# KA2_6.net
KiCad netlist of a schematic drawn in Altium Designer
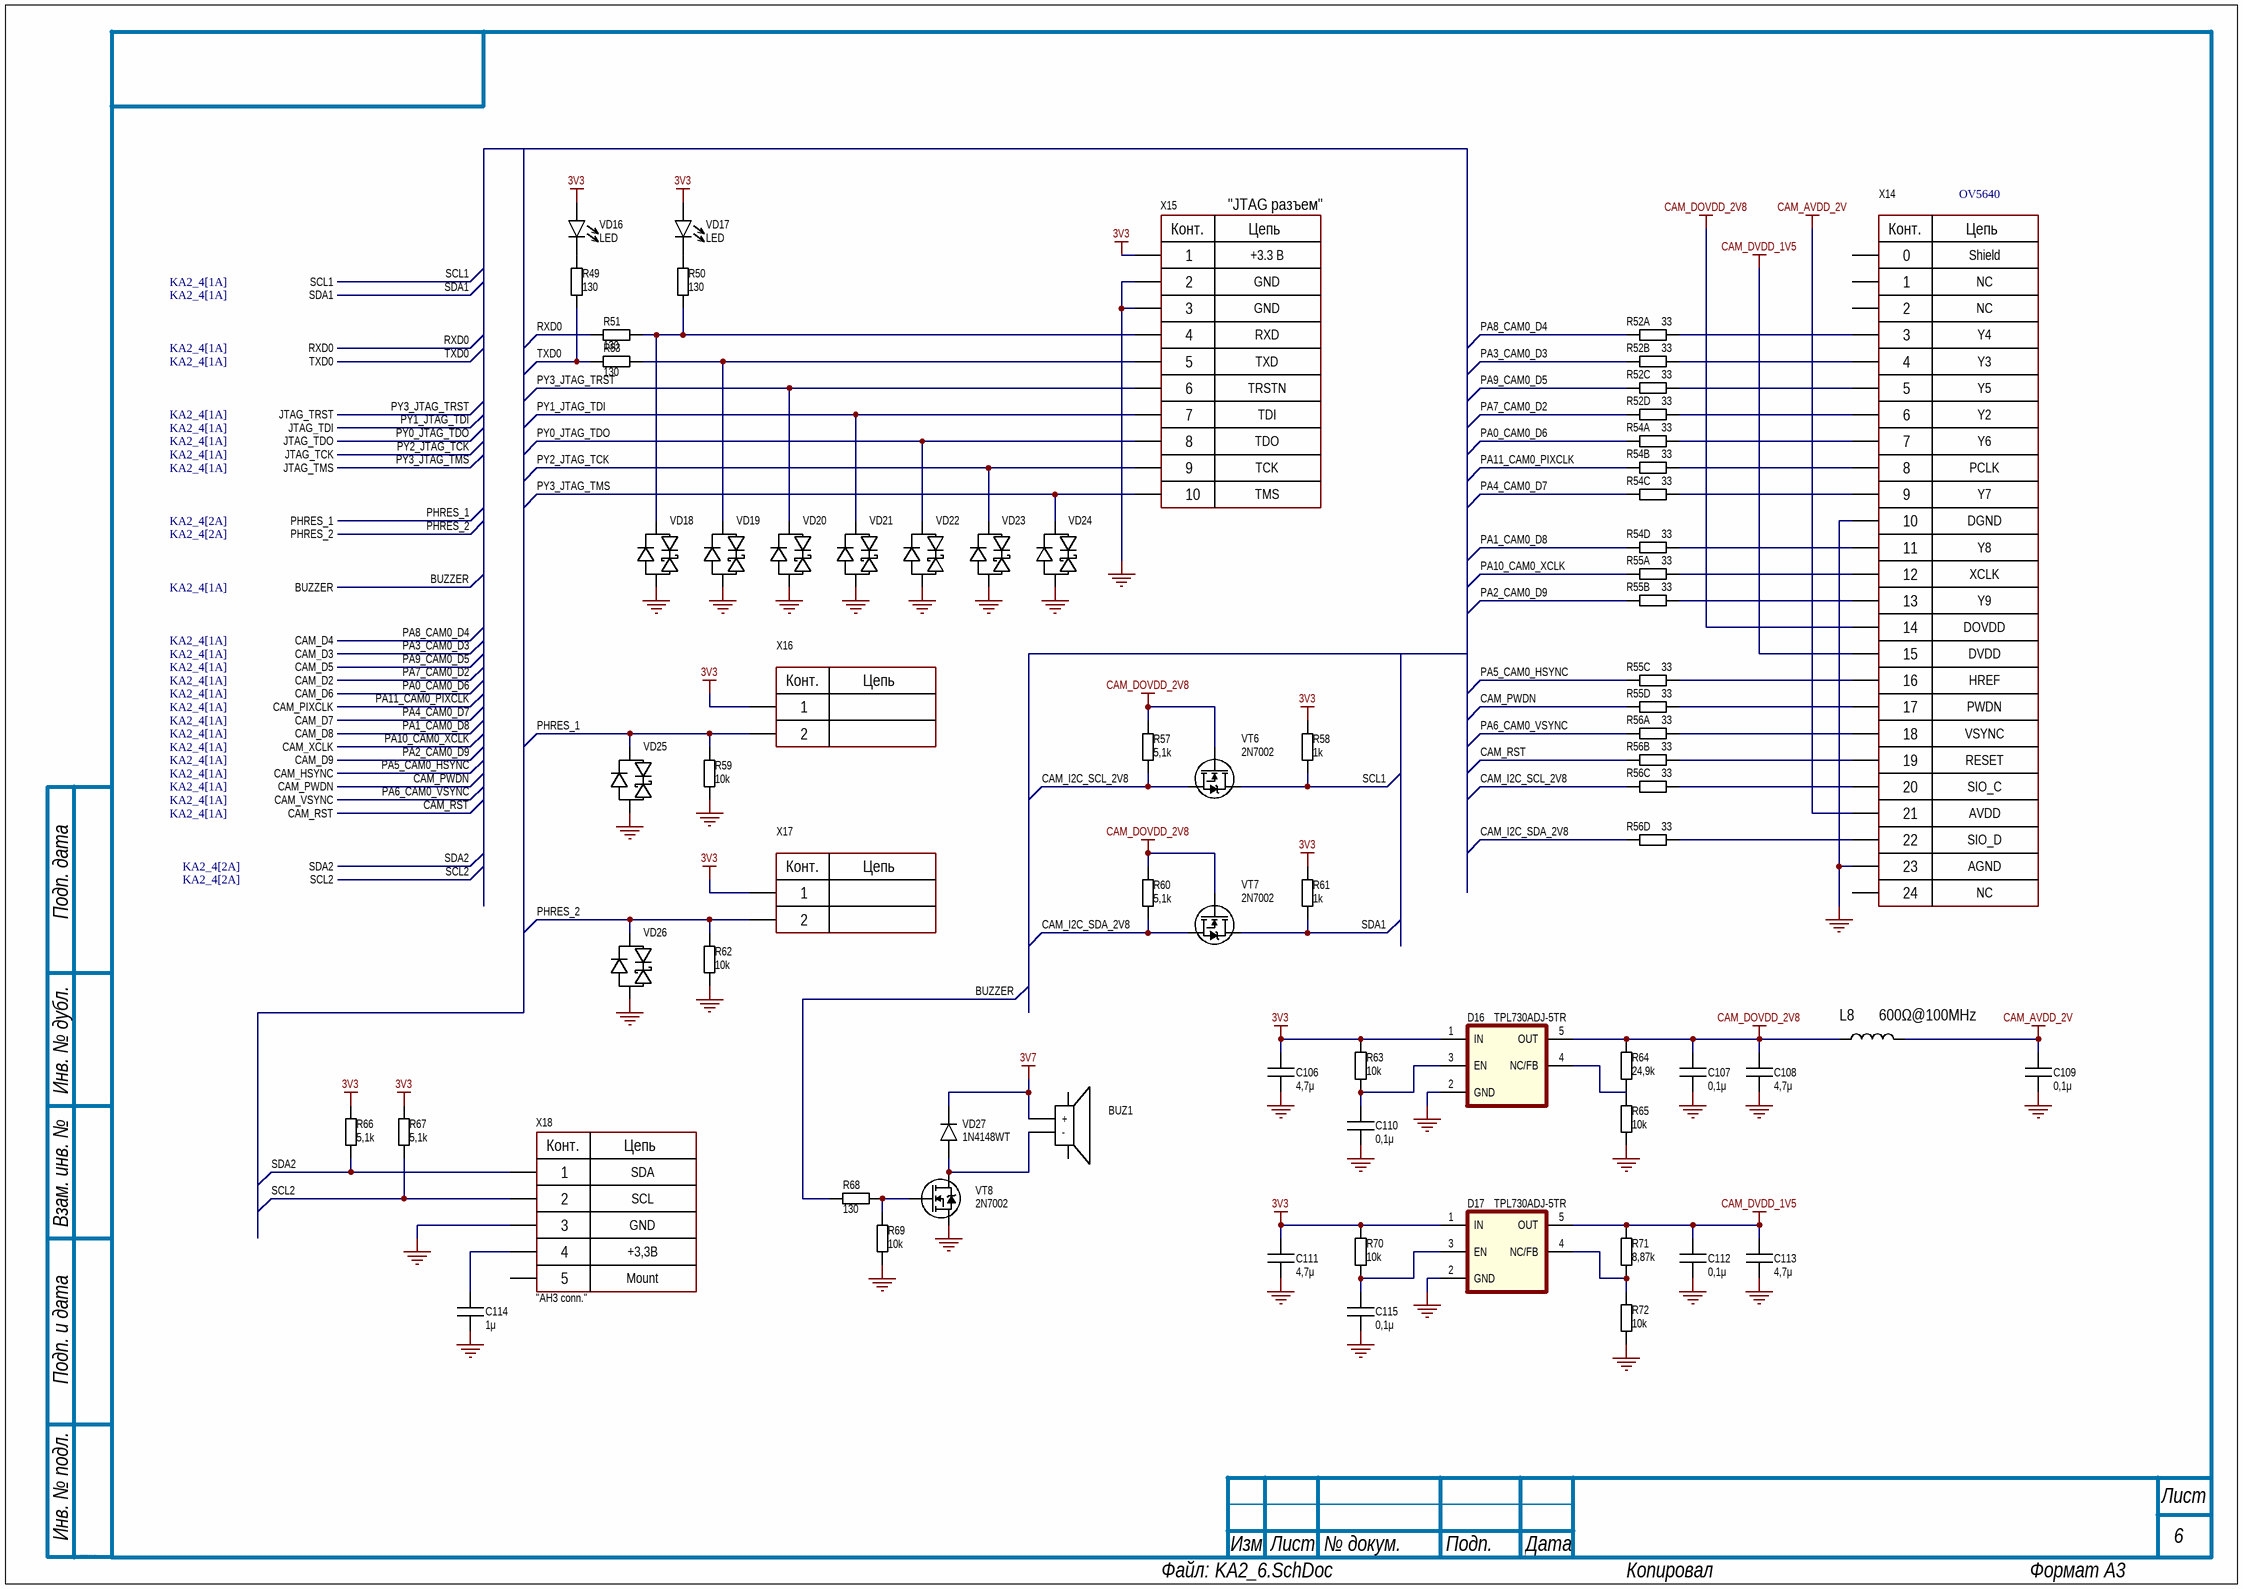
[diagram p0: KA2_6.SchDoc]

(export (version "E")
  (design (tool "Eeschema 10.0.6"))
  (components
    (comp (ref "BUZ1")
      (value "SMD7525-16Ohm")
      (footprint "BUZZER_SMD_7.5X7.5MM")
      (description "Буззер электромагнитный SMD, 7.5x7.5x2.5mm")
      (fields (field (name "MANUFACTURER") "XHXDZ") (field (name "MFR.PART") "SMD7525-16Ω"))
      (libsource (lib "Barsotion") (part "SMD7525-16Ohm"))
    )
    (comp (ref "C106")
      (value "4,7μ")
      (footprint "Capacitor_0402")
      (fields
        (field (name "VALUEMANUFACTURERPARTNUMBER") "Ceramic capacitor, 4,7μ, X7R, ±10%, 16V, 0402")
        (field (name "TOLERANCE") "±10%")
        (field (name "VOLTAGE") "16V")
      )
      (libsource (lib "Barsotion") (part "Ceramic_0402"))
    )
    (comp (ref "C107")
      (value "0,1μ")
      (footprint "Capacitor_0402")
      (fields
        (field (name "VALUEMANUFACTURERPARTNUMBER") "Ceramic capacitor, 0,1μ, X7R, ±10%, 16V, 0402")
        (field (name "TOLERANCE") "±10%")
        (field (name "VOLTAGE") "16V")
      )
      (libsource (lib "Barsotion") (part "Ceramic_0402"))
    )
    (comp (ref "C108")
      (value "4,7μ")
      (footprint "Capacitor_0402")
      (fields
        (field (name "VALUEMANUFACTURERPARTNUMBER") "Ceramic capacitor, 4,7μ, X7R, ±10%, 16V, 0402")
        (field (name "TOLERANCE") "±10%")
        (field (name "VOLTAGE") "16V")
      )
      (libsource (lib "Barsotion") (part "Ceramic_0402"))
    )
    (comp (ref "C109")
      (value "0,1μ")
      (footprint "Capacitor_0402")
      (fields
        (field (name "VALUEMANUFACTURERPARTNUMBER") "Ceramic capacitor, 0,1μ, X7R, ±10%, 16V, 0402")
        (field (name "TOLERANCE") "±10%")
        (field (name "VOLTAGE") "16V")
      )
      (libsource (lib "Barsotion") (part "Ceramic_0402"))
    )
    (comp (ref "C110")
      (value "0,1μ")
      (footprint "Capacitor_0402")
      (fields
        (field (name "VALUEMANUFACTURERPARTNUMBER") "Ceramic capacitor, 0,1μ, X7R, ±10%, 16V, 0402")
        (field (name "TOLERANCE") "±10%")
        (field (name "VOLTAGE") "16V")
      )
      (libsource (lib "Barsotion") (part "Ceramic_0402"))
    )
    (comp (ref "C111")
      (value "4,7μ")
      (footprint "Capacitor_0402")
      (fields
        (field (name "VALUEMANUFACTURERPARTNUMBER") "Ceramic capacitor, 4,7μ, X7R, ±10%, 16V, 0402")
        (field (name "TOLERANCE") "±10%")
        (field (name "VOLTAGE") "16V")
      )
      (libsource (lib "Barsotion") (part "Ceramic_0402"))
    )
    (comp (ref "C112")
      (value "0,1μ")
      (footprint "Capacitor_0402")
      (fields
        (field (name "VALUEMANUFACTURERPARTNUMBER") "Ceramic capacitor, 0,1μ, X7R, ±10%, 16V, 0402")
        (field (name "TOLERANCE") "±10%")
        (field (name "VOLTAGE") "16V")
      )
      (libsource (lib "Barsotion") (part "Ceramic_0402"))
    )
    (comp (ref "C113")
      (value "4,7μ")
      (footprint "Capacitor_0402")
      (fields
        (field (name "VALUEMANUFACTURERPARTNUMBER") "Ceramic capacitor, 4,7μ, X7R, ±10%, 16V, 0402")
        (field (name "TOLERANCE") "±10%")
        (field (name "VOLTAGE") "16V")
      )
      (libsource (lib "Barsotion") (part "Ceramic_0402"))
    )
    (comp (ref "C114")
      (value "1μ")
      (footprint "Capacitor_0402")
      (fields
        (field (name "VALUEMANUFACTURERPARTNUMBER") "Ceramic capacitor, 1μ, X7R, ±10%, 16V, 0402")
        (field (name "TOLERANCE") "±10%")
        (field (name "VOLTAGE") "16V")
      )
      (libsource (lib "Barsotion") (part "Ceramic_0402"))
    )
    (comp (ref "C115")
      (value "0,1μ")
      (footprint "Capacitor_0402")
      (fields
        (field (name "VALUEMANUFACTURERPARTNUMBER") "Ceramic capacitor, 0,1μ, X7R, ±10%, 16V, 0402")
        (field (name "TOLERANCE") "±10%")
        (field (name "VOLTAGE") "16V")
      )
      (libsource (lib "Barsotion") (part "Ceramic_0402"))
    )
    (comp (ref "D16")
      (value "TPL730ADJ-5TR")
      (footprint "SOT-23-5")
      (description "Микросхема драйвера импульсного понижающего преобразователя")
      (fields (field (name "MANUFACTURER") "3PEAK") (field (name "Comment") "TPL730ADJ-5TL"))
      (libsource (lib "Barsotion") (part "TPL730ADJ-5TL"))
    )
    (comp (ref "D17")
      (value "TPL730ADJ-5TR")
      (footprint "SOT-23-5")
      (description "Микросхема драйвера импульсного понижающего преобразователя")
      (fields (field (name "MANUFACTURER") "3PEAK") (field (name "Comment") "TPL730ADJ-5TL"))
      (libsource (lib "Barsotion") (part "TPL730ADJ-5TL"))
    )
    (comp (ref "L8")
      (value "600Ω@100MHz")
      (footprint "IND: 0603")
      (fields
        (field (name "TOLERANCE") "±10%")
        (field (name "VALUEMANUFACTURERPARTNUMBER") "Inductor, 600Ω@100MHz, ±10%, 0603")
      )
      (libsource (lib "Barsotion") (part "Inductor_0603"))
    )
    (comp (ref "R49")
      (value "130")
      (footprint "RES: 0402")
      (fields
        (field (name "VALUEMANUFACTURERPARTNUMBER") "Resistor, 130, ±1%, 0402")
        (field (name "TOLERANCE") "±1%")
      )
      (libsource (lib "Barsotion") (part "Resistor_0402"))
    )
    (comp (ref "R50")
      (value "130")
      (footprint "RES: 0402")
      (fields
        (field (name "VALUEMANUFACTURERPARTNUMBER") "Resistor, 130, ±1%, 0402")
        (field (name "TOLERANCE") "±1%")
      )
      (libsource (lib "Barsotion") (part "Resistor_0402"))
    )
    (comp (ref "R51")
      (value "130")
      (footprint "RES: 0402")
      (fields
        (field (name "VALUEMANUFACTURERPARTNUMBER") "Resistor, 130, ±1%, 0402")
        (field (name "TOLERANCE") "±1%")
      )
      (libsource (lib "") (part "Resistor_0402_1"))
    )
    (comp (ref "R52")
      (value "33")
      (footprint "Resistor:RES: Array 4x0402")
      (fields
        (field (name "VALUEMANUFACTURERPARTNUMBER") "Resistor array (4), 33, ±1%, 0402")
        (field (name "TOLERANCE") "±1%")
      )
      (libsource (lib "Barsotion") (part "ResistorArray_0402_4"))
    )
    (comp (ref "R53")
      (value "130")
      (footprint "RES: 0402")
      (fields
        (field (name "VALUEMANUFACTURERPARTNUMBER") "Resistor, 130, ±1%, 0402")
        (field (name "TOLERANCE") "±1%")
      )
      (libsource (lib "") (part "Resistor_0402_1"))
    )
    (comp (ref "R54")
      (value "33")
      (footprint "Resistor:RES: Array 4x0402")
      (fields
        (field (name "VALUEMANUFACTURERPARTNUMBER") "Resistor array (4), 33, ±1%, 0402")
        (field (name "TOLERANCE") "±1%")
      )
      (libsource (lib "Barsotion") (part "ResistorArray_0402_4"))
    )
    (comp (ref "R55")
      (value "33")
      (footprint "Resistor:RES: Array 4x0402")
      (fields
        (field (name "VALUEMANUFACTURERPARTNUMBER") "Resistor array (4), 33, ±1%, 0402")
        (field (name "TOLERANCE") "±1%")
      )
      (libsource (lib "Barsotion") (part "ResistorArray_0402_4"))
    )
    (comp (ref "R56")
      (value "33")
      (footprint "Resistor:RES: Array 4x0402")
      (fields
        (field (name "VALUEMANUFACTURERPARTNUMBER") "Resistor array (4), 33, ±1%, 0402")
        (field (name "TOLERANCE") "±1%")
      )
      (libsource (lib "Barsotion") (part "ResistorArray_0402_4"))
    )
    (comp (ref "R57")
      (value "5,1k")
      (footprint "RES: 0402")
      (fields
        (field (name "VALUEMANUFACTURERPARTNUMBER") "Resistor, 5,1k, ±1%, 0402")
        (field (name "TOLERANCE") "±1%")
      )
      (libsource (lib "Barsotion") (part "Resistor_0402"))
    )
    (comp (ref "R58")
      (value "1k")
      (footprint "RES: 0402")
      (fields
        (field (name "VALUEMANUFACTURERPARTNUMBER") "Resistor, 1k, ±1%, 0402")
        (field (name "TOLERANCE") "±1%")
      )
      (libsource (lib "Barsotion") (part "Resistor_0402"))
    )
    (comp (ref "R59")
      (value "10k")
      (footprint "RES: 0402")
      (fields
        (field (name "VALUEMANUFACTURERPARTNUMBER") "Resistor, 10k, ±1%, 0402")
        (field (name "TOLERANCE") "±1%")
      )
      (libsource (lib "Barsotion") (part "Resistor_0402"))
    )
    (comp (ref "R60")
      (value "5,1k")
      (footprint "RES: 0402")
      (fields
        (field (name "VALUEMANUFACTURERPARTNUMBER") "Resistor, 5,1k, ±1%, 0402")
        (field (name "TOLERANCE") "±1%")
      )
      (libsource (lib "Barsotion") (part "Resistor_0402"))
    )
    (comp (ref "R61")
      (value "1k")
      (footprint "RES: 0402")
      (fields
        (field (name "VALUEMANUFACTURERPARTNUMBER") "Resistor, 1k, ±1%, 0402")
        (field (name "TOLERANCE") "±1%")
      )
      (libsource (lib "Barsotion") (part "Resistor_0402"))
    )
    (comp (ref "R62")
      (value "10k")
      (footprint "RES: 0402")
      (fields
        (field (name "VALUEMANUFACTURERPARTNUMBER") "Resistor, 10k, ±1%, 0402")
        (field (name "TOLERANCE") "±1%")
      )
      (libsource (lib "Barsotion") (part "Resistor_0402"))
    )
    (comp (ref "R63")
      (value "10k")
      (footprint "RES: 0402")
      (fields
        (field (name "VALUEMANUFACTURERPARTNUMBER") "Resistor, 10k, ±1%, 0402")
        (field (name "TOLERANCE") "±1%")
      )
      (libsource (lib "Barsotion") (part "Resistor_0402"))
    )
    (comp (ref "R64")
      (value "24,9k")
      (footprint "RES: 0402")
      (fields
        (field (name "VALUEMANUFACTURERPARTNUMBER") "Resistor, 24,9k, ±1%, 0402")
        (field (name "TOLERANCE") "±1%")
      )
      (libsource (lib "Barsotion") (part "Resistor_0402"))
    )
    (comp (ref "R65")
      (value "10k")
      (footprint "RES: 0402")
      (fields
        (field (name "VALUEMANUFACTURERPARTNUMBER") "Resistor, 10k, ±1%, 0402")
        (field (name "TOLERANCE") "±1%")
      )
      (libsource (lib "Barsotion") (part "Resistor_0402"))
    )
    (comp (ref "R66")
      (value "5,1k")
      (footprint "RES: 0402")
      (fields
        (field (name "VALUEMANUFACTURERPARTNUMBER") "Resistor, 5,1k, ±1%, 0402")
        (field (name "TOLERANCE") "±1%")
      )
      (libsource (lib "Barsotion") (part "Resistor_0402"))
    )
    (comp (ref "R67")
      (value "5,1k")
      (footprint "RES: 0402")
      (fields
        (field (name "VALUEMANUFACTURERPARTNUMBER") "Resistor, 5,1k, ±1%, 0402")
        (field (name "TOLERANCE") "±1%")
      )
      (libsource (lib "Barsotion") (part "Resistor_0402"))
    )
    (comp (ref "R68")
      (value "130")
      (footprint "RES: 0402")
      (fields
        (field (name "VALUEMANUFACTURERPARTNUMBER") "Resistor, 130, ±1%, 0402")
        (field (name "TOLERANCE") "±1%")
      )
      (libsource (lib "") (part "Resistor_0402_1"))
    )
    (comp (ref "R69")
      (value "10k")
      (footprint "RES: 0402")
      (fields
        (field (name "VALUEMANUFACTURERPARTNUMBER") "Resistor, 10k, ±1%, 0402")
        (field (name "TOLERANCE") "±1%")
      )
      (libsource (lib "Barsotion") (part "Resistor_0402"))
    )
    (comp (ref "R70")
      (value "10k")
      (footprint "RES: 0402")
      (fields
        (field (name "VALUEMANUFACTURERPARTNUMBER") "Resistor, 10k, ±1%, 0402")
        (field (name "TOLERANCE") "±1%")
      )
      (libsource (lib "Barsotion") (part "Resistor_0402"))
    )
    (comp (ref "R71")
      (value "8,87k")
      (footprint "RES: 0402")
      (fields
        (field (name "VALUEMANUFACTURERPARTNUMBER") "Resistor, 8,87k, ±1%, 0402")
        (field (name "TOLERANCE") "±1%")
      )
      (libsource (lib "Barsotion") (part "Resistor_0402"))
    )
    (comp (ref "R72")
      (value "10k")
      (footprint "RES: 0402")
      (fields
        (field (name "VALUEMANUFACTURERPARTNUMBER") "Resistor, 10k, ±1%, 0402")
        (field (name "TOLERANCE") "±1%")
      )
      (libsource (lib "Barsotion") (part "Resistor_0402"))
    )
    (comp (ref "VD16")
      (value "LED")
      (footprint "LED: 0603Y")
      (description "Светодиод ледяной синий, 0603")
      (fields (field (name "MFR.PART") "A-SP192GB1D-A02-4T") (field (name "MANUFACTURER") "Amicc"))
      (libsource (lib "Barsotion") (part "LED_0603_IB"))
    )
    (comp (ref "VD17")
      (value "LED")
      (footprint "LED: 0603Y")
      (description "Светодиод изумрудно-зеленый, 0603")
      (fields (field (name "MFR.PART") "XL-1608UGC-04") (field (name "MANUFACTURER") "XINGLIGHT"))
      (libsource (lib "Barsotion") (part "LED_0603_EG"))
    )
    (comp (ref "VD18")
      (value "D1213A-01T")
      (footprint "SOD-523")
      (fields (field (name "MANUFACTURER") "Diodes") (field (name "MFR.PART") "D1213A-01T-7"))
      (libsource (lib "Barsotion") (part "D1213A-01T"))
    )
    (comp (ref "VD19")
      (value "D1213A-01T")
      (footprint "SOD-523")
      (fields (field (name "MANUFACTURER") "Diodes") (field (name "MFR.PART") "D1213A-01T-7"))
      (libsource (lib "Barsotion") (part "D1213A-01T"))
    )
    (comp (ref "VD20")
      (value "D1213A-01T")
      (footprint "SOD-523")
      (fields (field (name "MANUFACTURER") "Diodes") (field (name "MFR.PART") "D1213A-01T-7"))
      (libsource (lib "Barsotion") (part "D1213A-01T"))
    )
    (comp (ref "VD21")
      (value "D1213A-01T")
      (footprint "SOD-523")
      (fields (field (name "MANUFACTURER") "Diodes") (field (name "MFR.PART") "D1213A-01T-7"))
      (libsource (lib "Barsotion") (part "D1213A-01T"))
    )
    (comp (ref "VD22")
      (value "D1213A-01T")
      (footprint "SOD-523")
      (fields (field (name "MANUFACTURER") "Diodes") (field (name "MFR.PART") "D1213A-01T-7"))
      (libsource (lib "Barsotion") (part "D1213A-01T"))
    )
    (comp (ref "VD23")
      (value "D1213A-01T")
      (footprint "SOD-523")
      (fields (field (name "MANUFACTURER") "Diodes") (field (name "MFR.PART") "D1213A-01T-7"))
      (libsource (lib "Barsotion") (part "D1213A-01T"))
    )
    (comp (ref "VD24")
      (value "D1213A-01T")
      (footprint "SOD-523")
      (fields (field (name "MANUFACTURER") "Diodes") (field (name "MFR.PART") "D1213A-01T-7"))
      (libsource (lib "Barsotion") (part "D1213A-01T"))
    )
    (comp (ref "VD25")
      (value "D1213A-01T")
      (footprint "SOD-523")
      (fields (field (name "MANUFACTURER") "Diodes") (field (name "MFR.PART") "D1213A-01T-7"))
      (libsource (lib "Barsotion") (part "D1213A-01T"))
    )
    (comp (ref "VD26")
      (value "D1213A-01T")
      (footprint "SOD-523")
      (fields (field (name "MANUFACTURER") "Diodes") (field (name "MFR.PART") "D1213A-01T-7"))
      (libsource (lib "Barsotion") (part "D1213A-01T"))
    )
    (comp (ref "VD27")
      (value "1N4148WT")
      (footprint "SOD-523")
      (description "Диод кремниевый 100В 300мА, SOD-123")
      (fields
        (field (name "MANUFACTURER") "JSMSEMI")
        (field (name "Comment") "Diode Independent 75V 150mA Surface Mount SOD-523")
      )
      (libsource (lib "Barsotion") (part "1N4148WT"))
    )
    (comp (ref "VT6")
      (value "2N7002")
      (footprint "SOT-23")
      (description "Транзистор N-канальный, 60В 115мА 200мВт, SOT-23")
      (fields (field (name "MFR.PART") "2N7002K-7") (field (name "MANUFACTURER") "Diodes"))
      (libsource (lib "Barsotion") (part "2N7002"))
    )
    (comp (ref "VT7")
      (value "2N7002")
      (footprint "SOT-23")
      (description "Транзистор N-канальный, 60В 115мА 200мВт, SOT-23")
      (fields (field (name "MFR.PART") "2N7002K-7") (field (name "MANUFACTURER") "Diodes"))
      (libsource (lib "Barsotion") (part "2N7002"))
    )
    (comp (ref "VT8")
      (value "2N7002")
      (footprint "SOT-23")
      (description "Транзистор N-канальный, 60В 115мА 200мВт, SOT-23")
      (fields (field (name "MFR.PART") "2N7002K-7") (field (name "MANUFACTURER") "Diodes"))
      (libsource (lib "Barsotion") (part "2N7002"))
    )
    (comp (ref "X14")
      (value "OV5640")
      (footprint "OV5640_CONNECTOR")
      (fields
        (field (name "MANUFACTURER") "kinghelm")
        (field (name "MFR.PART") "KH-FG0.5-H2.0-24PIN")
        (field (name "Comment") "Connector_OV5640")
      )
      (libsource (lib "Barsotion") (part "Connector_OV5640"))
    )
    (comp (ref "X15")
      (value "~")
      (footprint "CONN_5x10_1.27мм_NO_SOLDERING")
      (description "Edge-board JTAG connector including TRST")
      (fields
        (field (name "MANUFACTURER") "JST")
        (field (name "VALUEMANUFACTURERPARTNUMBER") "Connector, 2pin, 2.5 mm, 250V, 3A")
        (field (name "COMMENTTEXT") "\"JTAG разъем\"")
      )
      (libsource (lib "Barsotion") (part "Connector_JTAG_10"))
    )
    (comp (ref "X16")
      (value "Connector_JST_XH_B2B-XH-A_1x02_2.50mm")
      (footprint "CONN_JST_XH_B2B-XH-A_1x02_P2.50mm")
      (description "2-pin through-hole connector")
      (libsource (lib "Barsotion") (part "Connector_JST_XH_B2B-XH-A_1x02_2.50mm"))
    )
    (comp (ref "X17")
      (value "Connector_JST_XH_B2B-XH-A_1x02_2.50mm")
      (footprint "CONN_JST_XH_B2B-XH-A_1x02_P2.50mm")
      (description "2-pin through-hole connector")
      (libsource (lib "Barsotion") (part "Connector_JST_XH_B2B-XH-A_1x02_2.50mm"))
    )
    (comp (ref "X18")
      (value "\"AH3 conn.\"")
      (footprint "CONN_JST_GH_SM04B")
      (description "Connector Header 4 position 1.25mm Pitch")
      (fields
        (field (name "MANUFACTURER") "CJT(Changjiang Connectors)")
        (field (name "MFR.PART") "A1257WR-S-4P")
      )
      (libsource (lib "Barsotion") (part "Connector_AH3"))
    )
  )
  (nets
    (net (code "1") (name "/BUZZER") (class "Default")
      (node (ref "R68") (pin "2") (pinfunction "2_2") (pintype "passive"))
    )
    (net (code "2") (name "/CAM_I2C_SCL_2V8") (class "Default")
      (node (ref "R56") (pin "3") (pinfunction "3_3") (pintype "passive"))
      (node (ref "R57") (pin "1") (pinfunction "1_1") (pintype "passive"))
      (node (ref "VT6") (pin "2") (pinfunction "S_2") (pintype "passive"))
    )
    (net (code "3") (name "/CAM_I2C_SDA_2V8") (class "Default")
      (node (ref "R56") (pin "4") (pinfunction "4_4") (pintype "passive"))
      (node (ref "R60") (pin "1") (pinfunction "1_1") (pintype "passive"))
      (node (ref "VT7") (pin "2") (pinfunction "S_2") (pintype "passive"))
    )
    (net (code "4") (name "/CAM_PWDN") (class "Default")
      (node (ref "R55") (pin "4") (pinfunction "4_4") (pintype "passive"))
    )
    (net (code "5") (name "/CAM_RST") (class "Default")
      (node (ref "R56") (pin "2") (pinfunction "2_2") (pintype "passive"))
    )
    (net (code "6") (name "/PA0_CAM0_D6") (class "Default")
      (node (ref "R54") (pin "1") (pinfunction "1_1") (pintype "passive"))
    )
    (net (code "7") (name "/PA1_CAM0_D8") (class "Default")
      (node (ref "R54") (pin "4") (pinfunction "4_4") (pintype "passive"))
    )
    (net (code "8") (name "/PA2_CAM0_D9") (class "Default")
      (node (ref "R55") (pin "2") (pinfunction "2_2") (pintype "passive"))
    )
    (net (code "9") (name "/PA3_CAM0_D3") (class "Default")
      (node (ref "R52") (pin "2") (pinfunction "2_2") (pintype "passive"))
    )
    (net (code "10") (name "/PA4_CAM0_D7") (class "Default")
      (node (ref "R54") (pin "3") (pinfunction "3_3") (pintype "passive"))
    )
    (net (code "11") (name "/PA5_CAM0_HSYNC") (class "Default")
      (node (ref "R55") (pin "3") (pinfunction "3_3") (pintype "passive"))
    )
    (net (code "12") (name "/PA6_CAM0_VSYNC") (class "Default")
      (node (ref "R56") (pin "1") (pinfunction "1_1") (pintype "passive"))
    )
    (net (code "13") (name "/PA7_CAM0_D2") (class "Default")
      (node (ref "R52") (pin "4") (pinfunction "4_4") (pintype "passive"))
    )
    (net (code "14") (name "/PA8_CAM0_D4") (class "Default")
      (node (ref "R52") (pin "1") (pinfunction "1_1") (pintype "passive"))
    )
    (net (code "15") (name "/PA9_CAM0_D5") (class "Default")
      (node (ref "R52") (pin "3") (pinfunction "3_3") (pintype "passive"))
    )
    (net (code "16") (name "/PA10_CAM0_XCLK") (class "Default")
      (node (ref "R55") (pin "1") (pinfunction "1_1") (pintype "passive"))
    )
    (net (code "17") (name "/PA11_CAM0_PIXCLK") (class "Default")
      (node (ref "R54") (pin "2") (pinfunction "2_2") (pintype "passive"))
    )
    (net (code "18") (name "/PHRES_1") (class "Default")
      (node (ref "R59") (pin "2") (pinfunction "2_2") (pintype "passive"))
      (node (ref "VD25") (pin "K") (pinfunction "K_K") (pintype "passive"))
      (node (ref "X16") (pin "2") (pinfunction "2_2") (pintype "passive"))
    )
    (net (code "19") (name "/PHRES_2") (class "Default")
      (node (ref "R62") (pin "2") (pinfunction "2_2") (pintype "passive"))
      (node (ref "VD26") (pin "K") (pinfunction "K_K") (pintype "passive"))
      (node (ref "X17") (pin "2") (pinfunction "2_2") (pintype "passive"))
    )
    (net (code "20") (name "/PY0_JTAG_TDO") (class "Default")
      (node (ref "VD22") (pin "K") (pinfunction "K_K") (pintype "passive"))
      (node (ref "X15") (pin "8") (pinfunction "8_8") (pintype "passive"))
    )
    (net (code "21") (name "/PY1_JTAG_TDI") (class "Default")
      (node (ref "VD21") (pin "K") (pinfunction "K_K") (pintype "passive"))
      (node (ref "X15") (pin "7") (pinfunction "7_7") (pintype "passive"))
    )
    (net (code "22") (name "/PY2_JTAG_TCK") (class "Default")
      (node (ref "VD23") (pin "K") (pinfunction "K_K") (pintype "passive"))
      (node (ref "X15") (pin "9") (pinfunction "9_9") (pintype "passive"))
    )
    (net (code "23") (name "/PY3_JTAG_TMS") (class "Default")
      (node (ref "VD24") (pin "K") (pinfunction "K_K") (pintype "passive"))
      (node (ref "X15") (pin "10") (pinfunction "10_10") (pintype "passive"))
    )
    (net (code "24") (name "/PY3_JTAG_TRST") (class "Default")
      (node (ref "VD20") (pin "K") (pinfunction "K_K") (pintype "passive"))
      (node (ref "X15") (pin "6") (pinfunction "6_6") (pintype "passive"))
    )
    (net (code "25") (name "/RXD0") (class "Default")
      (node (ref "R51") (pin "2") (pinfunction "2_2") (pintype "passive"))
    )
    (net (code "26") (name "/SCL1") (class "Default")
      (node (ref "R58") (pin "1") (pinfunction "1_1") (pintype "passive"))
      (node (ref "VT6") (pin "3") (pinfunction "D_3") (pintype "passive"))
    )
    (net (code "27") (name "/SCL2") (class "Default")
      (node (ref "R67") (pin "1") (pinfunction "1_1") (pintype "passive"))
      (node (ref "X18") (pin "2") (pinfunction "2_2") (pintype "passive"))
    )
    (net (code "28") (name "/SDA1") (class "Default")
      (node (ref "R61") (pin "1") (pinfunction "1_1") (pintype "passive"))
      (node (ref "VT7") (pin "3") (pinfunction "D_3") (pintype "passive"))
    )
    (net (code "29") (name "/SDA2") (class "Default")
      (node (ref "R66") (pin "1") (pinfunction "1_1") (pintype "passive"))
      (node (ref "X18") (pin "1") (pinfunction "1_1") (pintype "passive"))
    )
    (net (code "30") (name "/TXD0") (class "Default")
      (node (ref "R49") (pin "1") (pinfunction "1_1") (pintype "passive"))
      (node (ref "R53") (pin "2") (pinfunction "2_2") (pintype "passive"))
    )
    (net (code "31") (name "3V3") (class "Default")
      (node (ref "C106") (pin "2") (pinfunction "2_2") (pintype "passive"))
      (node (ref "C111") (pin "2") (pinfunction "2_2") (pintype "passive"))
      (node (ref "D16") (pin "1") (pinfunction "IN_1") (pintype "passive"))
      (node (ref "D17") (pin "1") (pinfunction "IN_1") (pintype "passive"))
      (node (ref "R58") (pin "2") (pinfunction "2_2") (pintype "passive"))
      (node (ref "R61") (pin "2") (pinfunction "2_2") (pintype "passive"))
      (node (ref "R63") (pin "2") (pinfunction "2_2") (pintype "passive"))
      (node (ref "R66") (pin "2") (pinfunction "2_2") (pintype "passive"))
      (node (ref "R67") (pin "2") (pinfunction "2_2") (pintype "passive"))
      (node (ref "R70") (pin "2") (pinfunction "2_2") (pintype "passive"))
      (node (ref "VD16") (pin "A") (pinfunction "Anode_A") (pintype "passive"))
      (node (ref "VD17") (pin "A") (pinfunction "Anode_A") (pintype "passive"))
      (node (ref "X15") (pin "1") (pinfunction "1_1") (pintype "passive"))
      (node (ref "X16") (pin "1") (pinfunction "1_1") (pintype "passive"))
      (node (ref "X17") (pin "1") (pinfunction "1_1") (pintype "passive"))
    )
    (net (code "32") (name "3V7") (class "Default")
      (node (ref "BUZ1") (pin "2") (pinfunction "+_2") (pintype "passive"))
      (node (ref "VD27") (pin "K") (pinfunction "Kathode_K") (pintype "passive"))
    )
    (net (code "33") (name "CAM_AVDD_2V") (class "Default")
      (node (ref "C109") (pin "2") (pinfunction "2_2") (pintype "passive"))
      (node (ref "L8") (pin "1") (pinfunction "1_1") (pintype "passive"))
      (node (ref "X14") (pin "21") (pinfunction "21_21") (pintype "passive"))
    )
    (net (code "34") (name "CAM_DOVDD_2V8") (class "Default")
      (node (ref "C107") (pin "2") (pinfunction "2_2") (pintype "passive"))
      (node (ref "C108") (pin "2") (pinfunction "2_2") (pintype "passive"))
      (node (ref "D16") (pin "5") (pinfunction "OUT_5") (pintype "passive"))
      (node (ref "L8") (pin "2") (pinfunction "2_2") (pintype "passive"))
      (node (ref "R57") (pin "2") (pinfunction "2_2") (pintype "passive"))
      (node (ref "R60") (pin "2") (pinfunction "2_2") (pintype "passive"))
      (node (ref "R64") (pin "2") (pinfunction "2_2") (pintype "passive"))
      (node (ref "VT6") (pin "1") (pinfunction "G_1") (pintype "passive"))
      (node (ref "VT7") (pin "1") (pinfunction "G_1") (pintype "passive"))
      (node (ref "X14") (pin "14") (pinfunction "14_14") (pintype "passive"))
    )
    (net (code "35") (name "CAM_DVDD_1V5") (class "Default")
      (node (ref "C112") (pin "2") (pinfunction "2_2") (pintype "passive"))
      (node (ref "C113") (pin "2") (pinfunction "2_2") (pintype "passive"))
      (node (ref "D17") (pin "5") (pinfunction "OUT_5") (pintype "passive"))
      (node (ref "R71") (pin "2") (pinfunction "2_2") (pintype "passive"))
      (node (ref "X14") (pin "15") (pinfunction "15_15") (pintype "passive"))
    )
    (net (code "36") (name "GND") (class "Default")
      (node (ref "C106") (pin "1") (pinfunction "1_1") (pintype "passive"))
      (node (ref "C107") (pin "1") (pinfunction "1_1") (pintype "passive"))
      (node (ref "C108") (pin "1") (pinfunction "1_1") (pintype "passive"))
      (node (ref "C109") (pin "1") (pinfunction "1_1") (pintype "passive"))
      (node (ref "C110") (pin "1") (pinfunction "1_1") (pintype "passive"))
      (node (ref "C111") (pin "1") (pinfunction "1_1") (pintype "passive"))
      (node (ref "C112") (pin "1") (pinfunction "1_1") (pintype "passive"))
      (node (ref "C113") (pin "1") (pinfunction "1_1") (pintype "passive"))
      (node (ref "C114") (pin "1") (pinfunction "1_1") (pintype "passive"))
      (node (ref "C115") (pin "1") (pinfunction "1_1") (pintype "passive"))
      (node (ref "D16") (pin "2") (pinfunction "GND_2") (pintype "passive"))
      (node (ref "D17") (pin "2") (pinfunction "GND_2") (pintype "passive"))
      (node (ref "R59") (pin "1") (pinfunction "1_1") (pintype "passive"))
      (node (ref "R62") (pin "1") (pinfunction "1_1") (pintype "passive"))
      (node (ref "R65") (pin "1") (pinfunction "1_1") (pintype "passive"))
      (node (ref "R69") (pin "1") (pinfunction "1_1") (pintype "passive"))
      (node (ref "R72") (pin "1") (pinfunction "1_1") (pintype "passive"))
      (node (ref "VD18") (pin "A") (pinfunction "A_A") (pintype "passive"))
      (node (ref "VD19") (pin "A") (pinfunction "A_A") (pintype "passive"))
      (node (ref "VD20") (pin "A") (pinfunction "A_A") (pintype "passive"))
      (node (ref "VD21") (pin "A") (pinfunction "A_A") (pintype "passive"))
      (node (ref "VD22") (pin "A") (pinfunction "A_A") (pintype "passive"))
      (node (ref "VD23") (pin "A") (pinfunction "A_A") (pintype "passive"))
      (node (ref "VD24") (pin "A") (pinfunction "A_A") (pintype "passive"))
      (node (ref "VD25") (pin "A") (pinfunction "A_A") (pintype "passive"))
      (node (ref "VD26") (pin "A") (pinfunction "A_A") (pintype "passive"))
      (node (ref "VT8") (pin "2") (pinfunction "S_2") (pintype "passive"))
      (node (ref "X14") (pin "10") (pinfunction "10_10") (pintype "passive"))
      (node (ref "X14") (pin "23") (pinfunction "23_23") (pintype "passive"))
      (node (ref "X15") (pin "2") (pinfunction "2_2") (pintype "passive"))
      (node (ref "X15") (pin "3") (pinfunction "3_3") (pintype "passive"))
      (node (ref "X18") (pin "3") (pinfunction "3_3") (pintype "passive"))
    )
    (net (code "37") (name "Net-(BUZ1--)") (class "Default")
      (node (ref "BUZ1") (pin "3") (pinfunction "-_3") (pintype "passive"))
      (node (ref "VD27") (pin "A") (pinfunction "Anode_A") (pintype "passive"))
      (node (ref "VT8") (pin "3") (pinfunction "D_3") (pintype "passive"))
    )
    (net (code "38") (name "Net-(C114-Pad2)") (class "Default")
      (node (ref "C114") (pin "2") (pinfunction "2_2") (pintype "passive"))
      (node (ref "X18") (pin "4") (pinfunction "4_4") (pintype "passive"))
    )
    (net (code "39") (name "Net-(D16-EN)") (class "Default")
      (node (ref "C110") (pin "2") (pinfunction "2_2") (pintype "passive"))
      (node (ref "D16") (pin "3") (pinfunction "EN_3") (pintype "passive"))
      (node (ref "R63") (pin "1") (pinfunction "1_1") (pintype "passive"))
    )
    (net (code "40") (name "Net-(D16-NC{slash}FB)") (class "Default")
      (node (ref "D16") (pin "4") (pinfunction "NC/FB_4") (pintype "passive"))
      (node (ref "R64") (pin "1") (pinfunction "1_1") (pintype "passive"))
      (node (ref "R65") (pin "2") (pinfunction "2_2") (pintype "passive"))
    )
    (net (code "41") (name "Net-(D17-EN)") (class "Default")
      (node (ref "C115") (pin "2") (pinfunction "2_2") (pintype "passive"))
      (node (ref "D17") (pin "3") (pinfunction "EN_3") (pintype "passive"))
      (node (ref "R70") (pin "1") (pinfunction "1_1") (pintype "passive"))
    )
    (net (code "42") (name "Net-(D17-NC{slash}FB)") (class "Default")
      (node (ref "D17") (pin "4") (pinfunction "NC/FB_4") (pintype "passive"))
      (node (ref "R71") (pin "1") (pinfunction "1_1") (pintype "passive"))
      (node (ref "R72") (pin "2") (pinfunction "2_2") (pintype "passive"))
    )
    (net (code "43") (name "Net-(R50-Pad1)") (class "Default")
      (node (ref "R50") (pin "1") (pinfunction "1_1") (pintype "passive"))
      (node (ref "R51") (pin "1") (pinfunction "1_1") (pintype "passive"))
      (node (ref "VD18") (pin "K") (pinfunction "K_K") (pintype "passive"))
      (node (ref "X15") (pin "4") (pinfunction "4_4") (pintype "passive"))
    )
    (net (code "44") (name "Net-(R52-Pad5)") (class "Default")
      (node (ref "R52") (pin "5") (pinfunction "5_5") (pintype "passive"))
      (node (ref "X14") (pin "6") (pinfunction "6_6") (pintype "passive"))
    )
    (net (code "45") (name "Net-(R52-Pad6)") (class "Default")
      (node (ref "R52") (pin "6") (pinfunction "6_6") (pintype "passive"))
      (node (ref "X14") (pin "5") (pinfunction "5_5") (pintype "passive"))
    )
    (net (code "46") (name "Net-(R52-Pad7)") (class "Default")
      (node (ref "R52") (pin "7") (pinfunction "7_7") (pintype "passive"))
      (node (ref "X14") (pin "4") (pinfunction "4_4") (pintype "passive"))
    )
    (net (code "47") (name "Net-(R52-Pad8)") (class "Default")
      (node (ref "R52") (pin "8") (pinfunction "8_8") (pintype "passive"))
      (node (ref "X14") (pin "3") (pinfunction "3_3") (pintype "passive"))
    )
    (net (code "48") (name "Net-(R53-Pad1)") (class "Default")
      (node (ref "R53") (pin "1") (pinfunction "1_1") (pintype "passive"))
      (node (ref "VD19") (pin "K") (pinfunction "K_K") (pintype "passive"))
      (node (ref "X15") (pin "5") (pinfunction "5_5") (pintype "passive"))
    )
    (net (code "49") (name "Net-(R54-Pad5)") (class "Default")
      (node (ref "R54") (pin "5") (pinfunction "5_5") (pintype "passive"))
      (node (ref "X14") (pin "11") (pinfunction "11_11") (pintype "passive"))
    )
    (net (code "50") (name "Net-(R54-Pad6)") (class "Default")
      (node (ref "R54") (pin "6") (pinfunction "6_6") (pintype "passive"))
      (node (ref "X14") (pin "9") (pinfunction "9_9") (pintype "passive"))
    )
    (net (code "51") (name "Net-(R54-Pad7)") (class "Default")
      (node (ref "R54") (pin "7") (pinfunction "7_7") (pintype "passive"))
      (node (ref "X14") (pin "8") (pinfunction "8_8") (pintype "passive"))
    )
    (net (code "52") (name "Net-(R54-Pad8)") (class "Default")
      (node (ref "R54") (pin "8") (pinfunction "8_8") (pintype "passive"))
      (node (ref "X14") (pin "7") (pinfunction "7_7") (pintype "passive"))
    )
    (net (code "53") (name "Net-(R55-Pad5)") (class "Default")
      (node (ref "R55") (pin "5") (pinfunction "5_5") (pintype "passive"))
      (node (ref "X14") (pin "17") (pinfunction "17_17") (pintype "passive"))
    )
    (net (code "54") (name "Net-(R55-Pad6)") (class "Default")
      (node (ref "R55") (pin "6") (pinfunction "6_6") (pintype "passive"))
      (node (ref "X14") (pin "16") (pinfunction "16_16") (pintype "passive"))
    )
    (net (code "55") (name "Net-(R55-Pad7)") (class "Default")
      (node (ref "R55") (pin "7") (pinfunction "7_7") (pintype "passive"))
      (node (ref "X14") (pin "13") (pinfunction "13_13") (pintype "passive"))
    )
    (net (code "56") (name "Net-(R55-Pad8)") (class "Default")
      (node (ref "R55") (pin "8") (pinfunction "8_8") (pintype "passive"))
      (node (ref "X14") (pin "12") (pinfunction "12_12") (pintype "passive"))
    )
    (net (code "57") (name "Net-(R56-Pad5)") (class "Default")
      (node (ref "R56") (pin "5") (pinfunction "5_5") (pintype "passive"))
      (node (ref "X14") (pin "22") (pinfunction "22_22") (pintype "passive"))
    )
    (net (code "58") (name "Net-(R56-Pad6)") (class "Default")
      (node (ref "R56") (pin "6") (pinfunction "6_6") (pintype "passive"))
      (node (ref "X14") (pin "20") (pinfunction "20_20") (pintype "passive"))
    )
    (net (code "59") (name "Net-(R56-Pad7)") (class "Default")
      (node (ref "R56") (pin "7") (pinfunction "7_7") (pintype "passive"))
      (node (ref "X14") (pin "19") (pinfunction "19_19") (pintype "passive"))
    )
    (net (code "60") (name "Net-(R56-Pad8)") (class "Default")
      (node (ref "R56") (pin "8") (pinfunction "8_8") (pintype "passive"))
      (node (ref "X14") (pin "18") (pinfunction "18_18") (pintype "passive"))
    )
    (net (code "61") (name "Net-(VD16-Kathode)") (class "Default")
      (node (ref "R49") (pin "2") (pinfunction "2_2") (pintype "passive"))
      (node (ref "VD16") (pin "K") (pinfunction "Kathode_K") (pintype "passive"))
    )
    (net (code "62") (name "Net-(VD17-Kathode)") (class "Default")
      (node (ref "R50") (pin "2") (pinfunction "2_2") (pintype "passive"))
      (node (ref "VD17") (pin "K") (pinfunction "Kathode_K") (pintype "passive"))
    )
    (net (code "63") (name "Net-(VT8-G)") (class "Default")
      (node (ref "R68") (pin "1") (pinfunction "1_1") (pintype "passive"))
      (node (ref "R69") (pin "2") (pinfunction "2_2") (pintype "passive"))
      (node (ref "VT8") (pin "1") (pinfunction "G_1") (pintype "passive"))
    )
    (net (code "64") (name "unconnected-(BUZ1-NC-Pad1)") (class "Default")
      (node (ref "BUZ1") (pin "1") (pinfunction "NC_1") (pintype "passive"))
    )
    (net (code "65") (name "unconnected-(BUZ1-NC-Pad4)") (class "Default")
      (node (ref "BUZ1") (pin "4") (pinfunction "NC_4") (pintype "passive"))
    )
    (net (code "66") (name "unconnected-(X14-Pad0)") (class "Default")
      (node (ref "X14") (pin "0") (pinfunction "0_0") (pintype "passive"))
    )
    (net (code "67") (name "unconnected-(X14-Pad1)") (class "Default")
      (node (ref "X14") (pin "1") (pinfunction "1_1") (pintype "passive"))
    )
    (net (code "68") (name "unconnected-(X14-Pad2)") (class "Default")
      (node (ref "X14") (pin "2") (pinfunction "2_2") (pintype "passive"))
    )
    (net (code "69") (name "unconnected-(X14-Pad24)") (class "Default")
      (node (ref "X14") (pin "24") (pinfunction "24_24") (pintype "passive"))
    )
    (net (code "70") (name "unconnected-(X18-Pad5)") (class "Default")
      (node (ref "X18") (pin "5") (pinfunction "5_5") (pintype "passive"))
    )
  )
)
